# Dual_ESC_6-24V_3_6A_V4_Easy_EDA.net
KiCad netlist of a schematic drawn in EasyEDA Pro
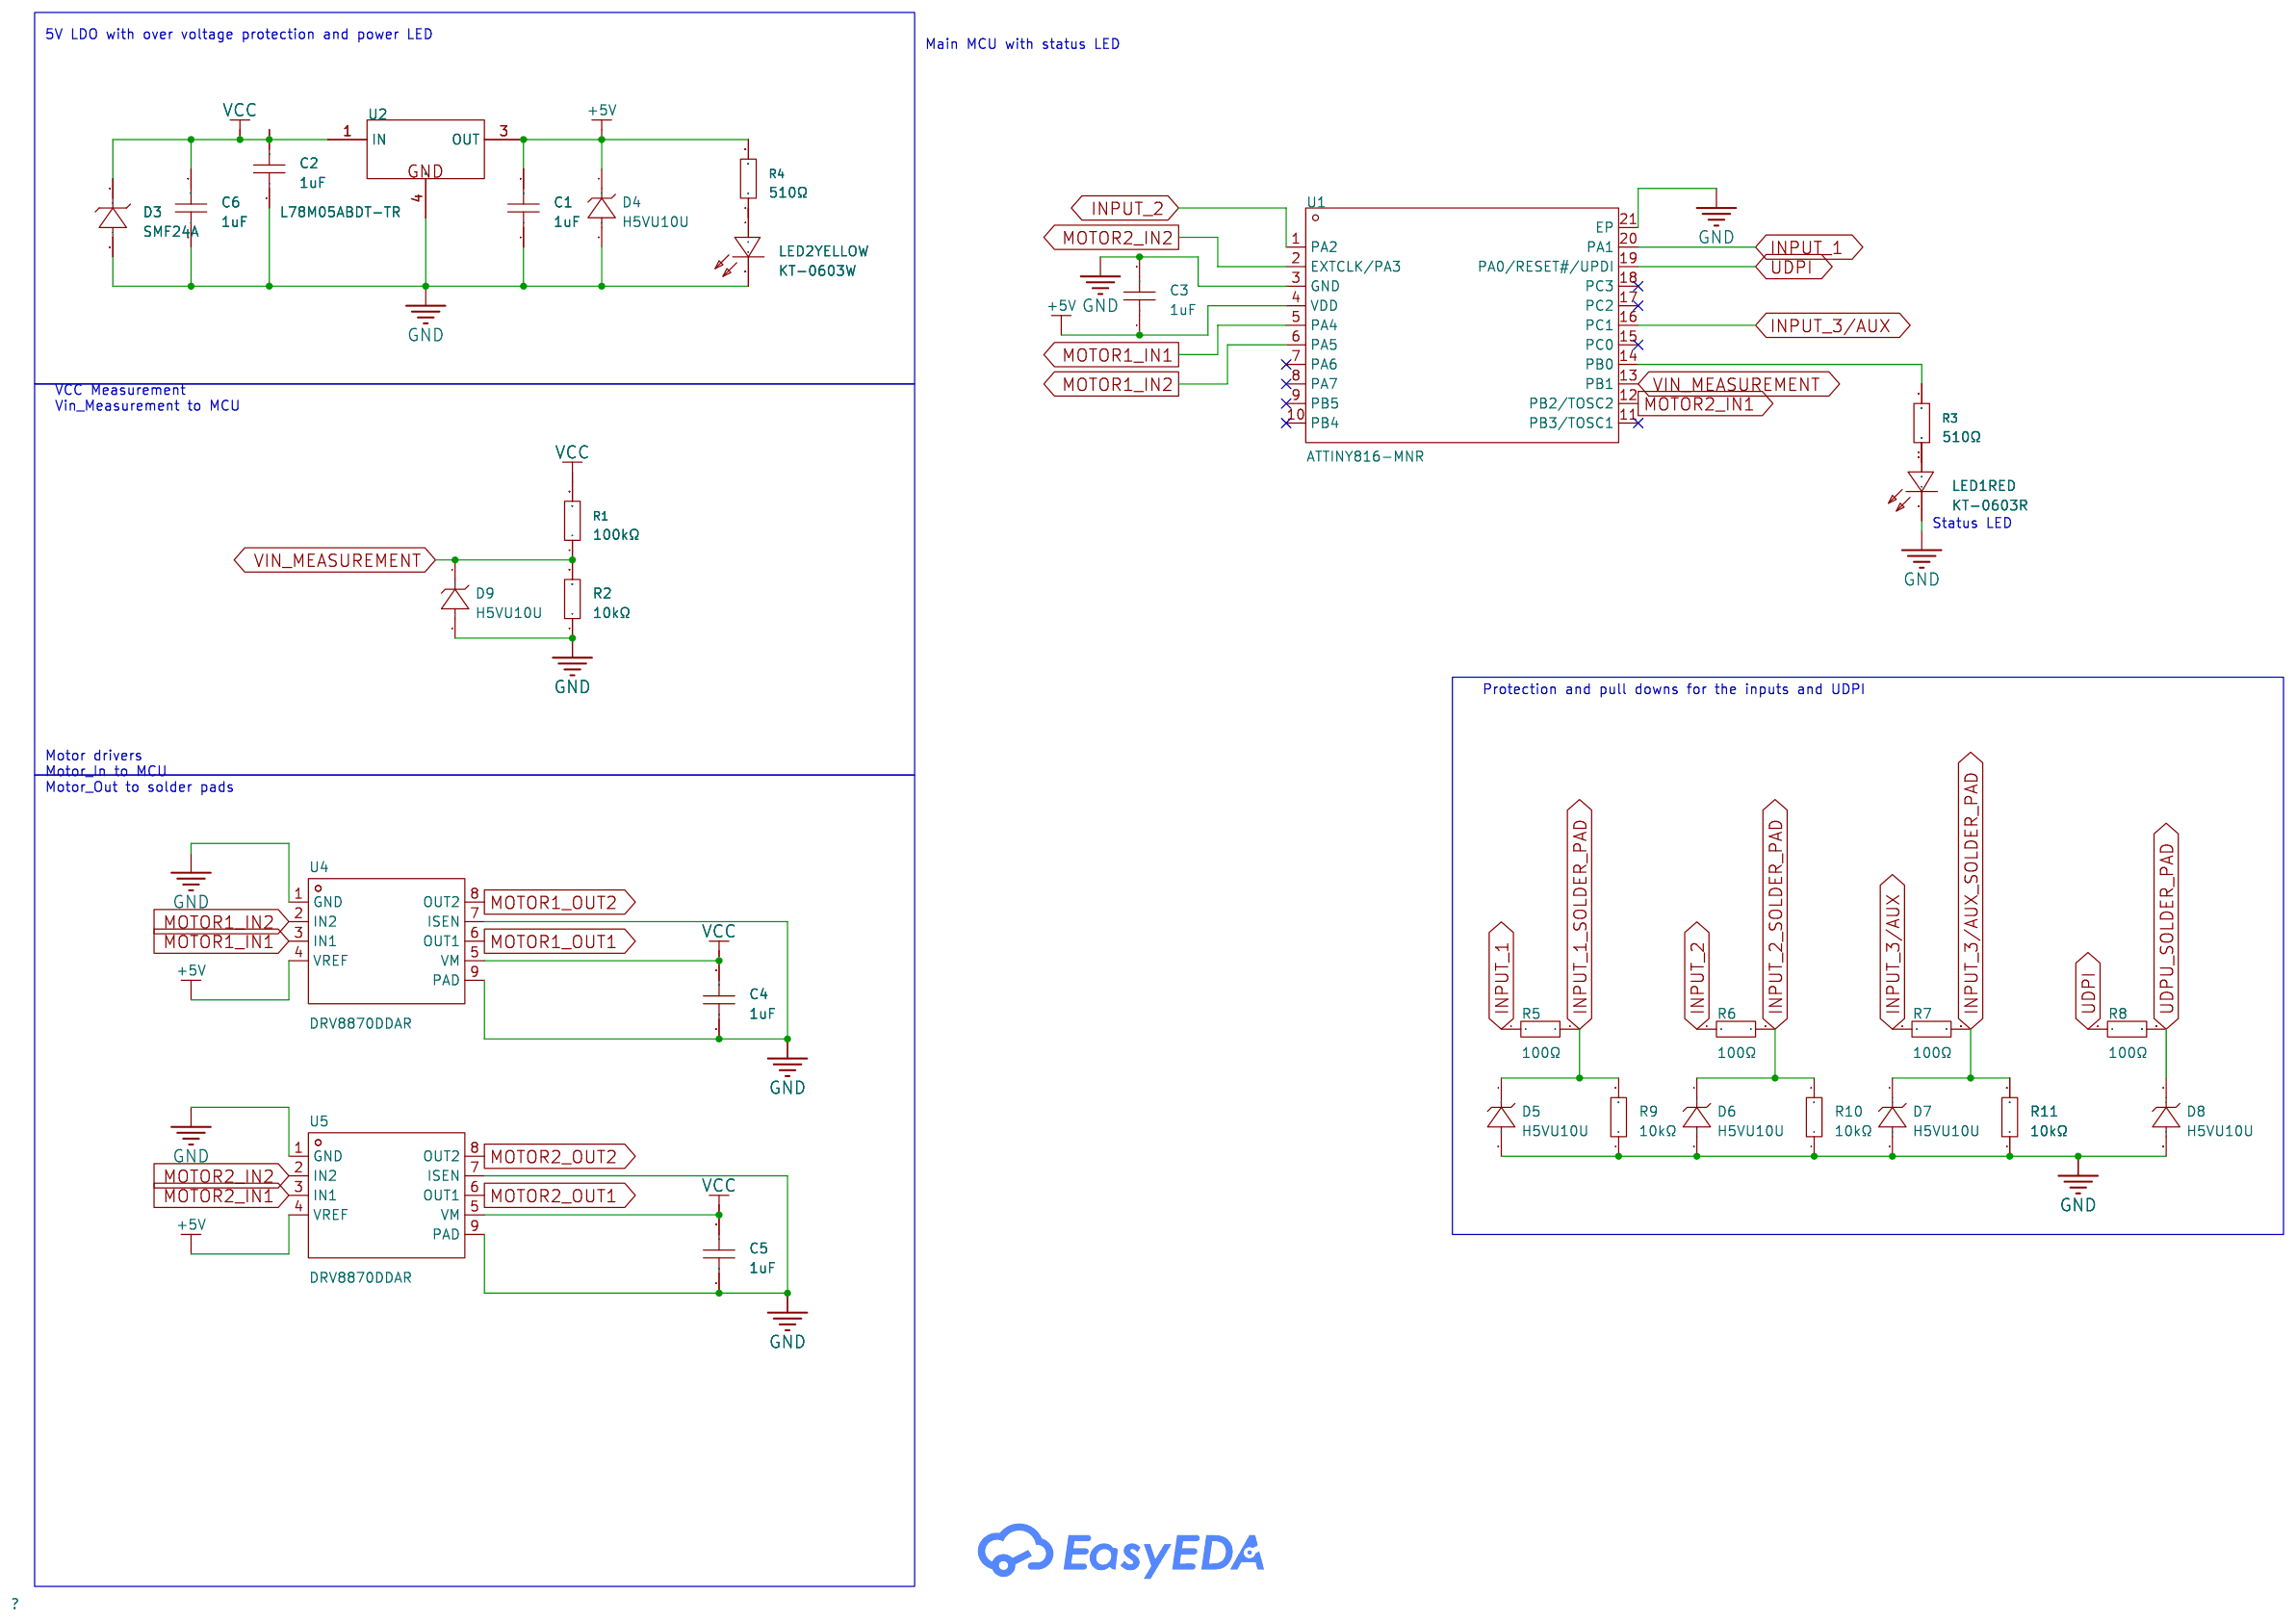
[diagram p0: schematic sheet]

(export (version "E")
  (design (tool "Eeschema 10.0.6"))
  (components
    (comp (ref "C1")
      (value "1uF")
      (footprint "easyedapro:C0402")
      (description "Capacitance:1uF Tolerance:±10% Tolerance:±10% Voltage Rating:25V Temperature Coefficient:X5R")
      (fields
        (field (name "Manufacturer Part") "CL05A105KA5NQNC")
        (field (name "Manufacturer") "SAMSUNG(三星)")
      )
      (libsource (lib "easyedapro") (part "CL05A105KA5NQNC"))
    )
    (comp (ref "C2")
      (value "1uF")
      (footprint "easyedapro:C0603")
      (description "Capacitance:1uF Tolerance:±10% Tolerance:±10% Voltage Rating:50V Temperature Coefficient:X5R")
      (fields
        (field (name "Manufacturer Part") "CL10A105KB8NNNC")
        (field (name "Manufacturer") "SAMSUNG(三星)")
      )
      (libsource (lib "easyedapro") (part "CL10A105KB8NNNC"))
    )
    (comp (ref "C3")
      (value "1uF")
      (footprint "easyedapro:C0402")
      (description "Capacitance:1uF Tolerance:±10% Tolerance:±10% Voltage Rating:25V Temperature Coefficient:X5R")
      (fields
        (field (name "Manufacturer Part") "CL05A105KA5NQNC")
        (field (name "Manufacturer") "SAMSUNG(三星)")
      )
      (libsource (lib "easyedapro") (part "CL05A105KA5NQNC"))
    )
    (comp (ref "C4")
      (value "1uF")
      (footprint "easyedapro:C0603")
      (description "Capacitance:1uF Tolerance:±10% Tolerance:±10% Voltage Rating:50V Temperature Coefficient:X5R")
      (fields
        (field (name "Manufacturer Part") "CL10A105KB8NNNC")
        (field (name "Manufacturer") "SAMSUNG(三星)")
      )
      (libsource (lib "easyedapro") (part "CL10A105KB8NNNC"))
    )
    (comp (ref "C5")
      (value "1uF")
      (footprint "easyedapro:C0603")
      (description "Capacitance:1uF Tolerance:±10% Tolerance:±10% Voltage Rating:50V Temperature Coefficient:X5R")
      (fields
        (field (name "Manufacturer Part") "CL10A105KB8NNNC")
        (field (name "Manufacturer") "SAMSUNG(三星)")
      )
      (libsource (lib "easyedapro") (part "CL10A105KB8NNNC"))
    )
    (comp (ref "C6")
      (value "1uF")
      (footprint "easyedapro:C0603")
      (description "Capacitance:1uF Tolerance:±10% Tolerance:±10% Voltage Rating:50V Temperature Coefficient:X5R")
      (fields
        (field (name "Manufacturer Part") "CL10A105KB8NNNC")
        (field (name "Manufacturer") "SAMSUNG(三星)")
      )
      (libsource (lib "easyedapro") (part "CL10A105KB8NNNC"))
    )
    (comp (ref "D3")
      (value "SMF24A")
      (footprint "easyedapro:SOD-123FL_L2.7-W1.8-LS3.8-RD")
      (fields (field (name "Manufacturer") "R+O(宏嘉诚)"))
      (libsource (lib "easyedapro") (part "SMF24A_C19077514"))
    )
    (comp (ref "D4")
      (value "H5VU10U")
      (footprint "easyedapro:DFN1006-2L-RD")
      (fields (field (name "Manufacturer") "R+O(宏嘉诚)"))
      (libsource (lib "easyedapro") (part "H5VU10U"))
    )
    (comp (ref "D5")
      (value "H5VU10U")
      (footprint "easyedapro:DFN1006-2L-RD")
      (fields (field (name "Manufacturer") "R+O(宏嘉诚)"))
      (libsource (lib "easyedapro") (part "H5VU10U"))
    )
    (comp (ref "D6")
      (value "H5VU10U")
      (footprint "easyedapro:DFN1006-2L-RD")
      (fields (field (name "Manufacturer") "R+O(宏嘉诚)"))
      (libsource (lib "easyedapro") (part "H5VU10U"))
    )
    (comp (ref "D7")
      (value "H5VU10U")
      (footprint "easyedapro:DFN1006-2L-RD")
      (fields (field (name "Manufacturer") "R+O(宏嘉诚)"))
      (libsource (lib "easyedapro") (part "H5VU10U"))
    )
    (comp (ref "D8")
      (value "H5VU10U")
      (footprint "easyedapro:DFN1006-2L-RD")
      (fields (field (name "Manufacturer") "R+O(宏嘉诚)"))
      (libsource (lib "easyedapro") (part "H5VU10U"))
    )
    (comp (ref "D9")
      (value "H5VU10U")
      (footprint "easyedapro:DFN1006-2L-RD")
      (fields (field (name "Manufacturer") "R+O(宏嘉诚)"))
      (libsource (lib "easyedapro") (part "H5VU10U"))
    )
    (comp (ref "LED1RED")
      (value "KT-0603R")
      (footprint "easyedapro:LED0603-RD")
      (fields (field (name "Manufacturer") "KENTO"))
      (libsource (lib "easyedapro") (part "KT-0603R"))
    )
    (comp (ref "LED2YELLOW")
      (value "KT-0603W")
      (footprint "easyedapro:LED0603-R-RD_WHITE")
      (fields (field (name "Manufacturer") "KENTO"))
      (libsource (lib "easyedapro") (part "0603White light_C2290"))
    )
    (comp (ref "R1")
      (value "100kΩ")
      (footprint "easyedapro:R0402")
      (fields
        (field (name "Manufacturer Part") "0402WGF1003TCE")
        (field (name "Manufacturer") "UNI-ROYAL(厚声)")
      )
      (libsource (lib "easyedapro") (part "0402WGF1003TCE"))
    )
    (comp (ref "R2")
      (value "10kΩ")
      (footprint "easyedapro:R0402")
      (fields
        (field (name "Manufacturer Part") "0402WGF1002TCE")
        (field (name "Manufacturer") "UNI-ROYAL(厚声)")
      )
      (libsource (lib "easyedapro") (part "0402WGF1002TCE"))
    )
    (comp (ref "R3")
      (value "510Ω")
      (footprint "easyedapro:R0402")
      (fields
        (field (name "Manufacturer Part") "0402WGF5100TCE")
        (field (name "Manufacturer") "UNI-ROYAL(厚声)")
      )
      (libsource (lib "easyedapro") (part "0402WGF5100TCE"))
    )
    (comp (ref "R4")
      (value "510Ω")
      (footprint "easyedapro:R0402")
      (fields
        (field (name "Manufacturer Part") "0402WGF5100TCE")
        (field (name "Manufacturer") "UNI-ROYAL(厚声)")
      )
      (libsource (lib "easyedapro") (part "0402WGF5100TCE"))
    )
    (comp (ref "R5")
      (value "100Ω")
      (footprint "easyedapro:R0402")
      (fields
        (field (name "Manufacturer Part") "0402WGF1000TCE")
        (field (name "Manufacturer") "UNI-ROYAL(厚声)")
      )
      (libsource (lib "easyedapro") (part "0402WGF1000TCE"))
    )
    (comp (ref "R6")
      (value "100Ω")
      (footprint "easyedapro:R0402")
      (fields
        (field (name "Manufacturer Part") "0402WGF1000TCE")
        (field (name "Manufacturer") "UNI-ROYAL(厚声)")
      )
      (libsource (lib "easyedapro") (part "0402WGF1000TCE"))
    )
    (comp (ref "R7")
      (value "100Ω")
      (footprint "easyedapro:R0402")
      (fields
        (field (name "Manufacturer Part") "0402WGF1000TCE")
        (field (name "Manufacturer") "UNI-ROYAL(厚声)")
      )
      (libsource (lib "easyedapro") (part "0402WGF1000TCE"))
    )
    (comp (ref "R8")
      (value "100Ω")
      (footprint "easyedapro:R0402")
      (fields
        (field (name "Manufacturer Part") "0402WGF1000TCE")
        (field (name "Manufacturer") "UNI-ROYAL(厚声)")
      )
      (libsource (lib "easyedapro") (part "0402WGF1000TCE"))
    )
    (comp (ref "R9")
      (value "10kΩ")
      (footprint "easyedapro:R0402")
      (fields
        (field (name "Manufacturer Part") "0402WGF1002TCE")
        (field (name "Manufacturer") "UNI-ROYAL(厚声)")
      )
      (libsource (lib "easyedapro") (part "0402WGF1002TCE"))
    )
    (comp (ref "R10")
      (value "10kΩ")
      (footprint "easyedapro:R0402")
      (fields
        (field (name "Manufacturer Part") "0402WGF1002TCE")
        (field (name "Manufacturer") "UNI-ROYAL(厚声)")
      )
      (libsource (lib "easyedapro") (part "0402WGF1002TCE"))
    )
    (comp (ref "R11")
      (value "10kΩ")
      (footprint "easyedapro:R0402")
      (fields
        (field (name "Manufacturer Part") "0402WGF1002TCE")
        (field (name "Manufacturer") "UNI-ROYAL(厚声)")
      )
      (libsource (lib "easyedapro") (part "0402WGF1002TCE"))
    )
    (comp (ref "U1")
      (value "ATTINY816-MNR")
      (fields (field (name "Manufacturer") "MICROCHIP(美国微芯)"))
      (libsource (lib "easyedapro") (part "ATTINY1616-MNR"))
    )
    (comp (ref "U2")
      (value "L78M05ABDT-TR")
      (footprint "easyedapro:TO-252-2_L6.5-W6.1-P4.58-LS10.0-TL")
      (fields (field (name "Manufacturer") "ST(意法半导体)"))
      (libsource (lib "easyedapro") (part "L78M05ABDT-TR"))
    )
    (comp (ref "U4")
      (value "DRV8870DDAR")
      (footprint "easyedapro:HSOP-8_L5.0-W4.0-P1.27-LS6.2-BL-EP")
      (fields (field (name "Manufacturer") "TI(德州仪器)"))
      (libsource (lib "easyedapro") (part "DRV8870DDAR"))
    )
    (comp (ref "U5")
      (value "DRV8870DDAR")
      (footprint "easyedapro:HSOP-8_L5.0-W4.0-P1.27-LS6.2-BL-EP")
      (fields (field (name "Manufacturer") "TI(德州仪器)"))
      (libsource (lib "easyedapro") (part "DRV8870DDAR"))
    )
  )
  (nets
    (net (code "1") (name "+5V") (class "Default")
      (node (ref "C1") (pin "2") (pinfunction "2_2") (pintype "unspecified"))
      (node (ref "C3") (pin "1") (pinfunction "1_1") (pintype "unspecified"))
      (node (ref "D4") (pin "1") (pinfunction "K_1") (pintype "unspecified"))
      (node (ref "R4") (pin "2") (pinfunction "2_2") (pintype "input"))
      (node (ref "U1") (pin "4") (pinfunction "VDD_4") (pintype "unspecified"))
      (node (ref "U2") (pin "3") (pinfunction "OUT_3") (pintype "unspecified"))
      (node (ref "U4") (pin "4") (pinfunction "VREF_4") (pintype "unspecified"))
      (node (ref "U5") (pin "4") (pinfunction "VREF_4") (pintype "unspecified"))
    )
    (net (code "2") (name "GND") (class "Default")
      (node (ref "C1") (pin "1") (pinfunction "1_1") (pintype "unspecified"))
      (node (ref "C2") (pin "1") (pinfunction "1_1") (pintype "unspecified"))
      (node (ref "C3") (pin "2") (pinfunction "2_2") (pintype "unspecified"))
      (node (ref "C4") (pin "1") (pinfunction "1_1") (pintype "unspecified"))
      (node (ref "C5") (pin "1") (pinfunction "1_1") (pintype "unspecified"))
      (node (ref "C6") (pin "1") (pinfunction "1_1") (pintype "unspecified"))
      (node (ref "D3") (pin "2") (pinfunction "A_2") (pintype "unspecified"))
      (node (ref "D4") (pin "2") (pinfunction "A_2") (pintype "unspecified"))
      (node (ref "D5") (pin "2") (pinfunction "A_2") (pintype "unspecified"))
      (node (ref "D6") (pin "2") (pinfunction "A_2") (pintype "unspecified"))
      (node (ref "D7") (pin "2") (pinfunction "A_2") (pintype "unspecified"))
      (node (ref "D8") (pin "2") (pinfunction "A_2") (pintype "unspecified"))
      (node (ref "D9") (pin "2") (pinfunction "A_2") (pintype "unspecified"))
      (node (ref "LED1RED") (pin "1") (pinfunction "K_1") (pintype "unspecified"))
      (node (ref "LED2YELLOW") (pin "2") (pinfunction "K_2") (pintype "unspecified"))
      (node (ref "R10") (pin "1") (pinfunction "1_1") (pintype "input"))
      (node (ref "R11") (pin "1") (pinfunction "1_1") (pintype "input"))
      (node (ref "R2") (pin "1") (pinfunction "1_1") (pintype "input"))
      (node (ref "R9") (pin "1") (pinfunction "1_1") (pintype "input"))
      (node (ref "U1") (pin "21") (pinfunction "EP_21") (pintype "unspecified"))
      (node (ref "U1") (pin "3") (pinfunction "GND_3") (pintype "unspecified"))
      (node (ref "U2") (pin "4") (pinfunction "GND_4") (pintype "unspecified"))
      (node (ref "U4") (pin "1") (pinfunction "GND_1") (pintype "unspecified"))
      (node (ref "U4") (pin "7") (pinfunction "ISEN_7") (pintype "unspecified"))
      (node (ref "U4") (pin "9") (pinfunction "PAD_9") (pintype "unspecified"))
      (node (ref "U5") (pin "1") (pinfunction "GND_1") (pintype "unspecified"))
      (node (ref "U5") (pin "7") (pinfunction "ISEN_7") (pintype "unspecified"))
      (node (ref "U5") (pin "9") (pinfunction "PAD_9") (pintype "unspecified"))
    )
    (net (code "3") (name "INPUT_1") (class "Default")
      (node (ref "R5") (pin "1") (pinfunction "1_1") (pintype "input"))
      (node (ref "U1") (pin "20") (pinfunction "PA1_20") (pintype "unspecified"))
    )
    (net (code "4") (name "INPUT_1_SOLDER_PAD") (class "Default")
      (node (ref "D5") (pin "1") (pinfunction "K_1") (pintype "unspecified"))
      (node (ref "R5") (pin "2") (pinfunction "2_2") (pintype "input"))
      (node (ref "R9") (pin "2") (pinfunction "2_2") (pintype "input"))
    )
    (net (code "5") (name "INPUT_2") (class "Default")
      (node (ref "R6") (pin "1") (pinfunction "1_1") (pintype "input"))
      (node (ref "U1") (pin "1") (pinfunction "PA2_1") (pintype "unspecified"))
    )
    (net (code "6") (name "INPUT_2_SOLDER_PAD") (class "Default")
      (node (ref "D6") (pin "1") (pinfunction "K_1") (pintype "unspecified"))
      (node (ref "R10") (pin "2") (pinfunction "2_2") (pintype "input"))
      (node (ref "R6") (pin "2") (pinfunction "2_2") (pintype "input"))
    )
    (net (code "7") (name "INPUT_3{slash}AUX") (class "Default")
      (node (ref "R7") (pin "1") (pinfunction "1_1") (pintype "input"))
      (node (ref "U1") (pin "16") (pinfunction "PC1_16") (pintype "unspecified"))
    )
    (net (code "8") (name "INPUT_3{slash}AUX_SOLDER_PAD") (class "Default")
      (node (ref "D7") (pin "1") (pinfunction "K_1") (pintype "unspecified"))
      (node (ref "R11") (pin "2") (pinfunction "2_2") (pintype "input"))
      (node (ref "R7") (pin "2") (pinfunction "2_2") (pintype "input"))
    )
    (net (code "9") (name "MOTOR1_IN1") (class "Default")
      (node (ref "U1") (pin "5") (pinfunction "PA4_5") (pintype "unspecified"))
      (node (ref "U4") (pin "3") (pinfunction "IN1_3") (pintype "unspecified"))
    )
    (net (code "10") (name "MOTOR1_IN2") (class "Default")
      (node (ref "U1") (pin "6") (pinfunction "PA5_6") (pintype "unspecified"))
      (node (ref "U4") (pin "2") (pinfunction "IN2_2") (pintype "unspecified"))
    )
    (net (code "11") (name "MOTOR1_OUT1") (class "Default")
      (node (ref "U4") (pin "6") (pinfunction "OUT1_6") (pintype "unspecified"))
    )
    (net (code "12") (name "MOTOR1_OUT2") (class "Default")
      (node (ref "U4") (pin "8") (pinfunction "OUT2_8") (pintype "unspecified"))
    )
    (net (code "13") (name "MOTOR2_IN1") (class "Default")
      (node (ref "U1") (pin "12") (pinfunction "PB2/TOSC2_12") (pintype "unspecified"))
      (node (ref "U5") (pin "3") (pinfunction "IN1_3") (pintype "unspecified"))
    )
    (net (code "14") (name "MOTOR2_IN2") (class "Default")
      (node (ref "U1") (pin "2") (pinfunction "EXTCLK/PA3_2") (pintype "unspecified"))
      (node (ref "U5") (pin "2") (pinfunction "IN2_2") (pintype "unspecified"))
    )
    (net (code "15") (name "MOTOR2_OUT1") (class "Default")
      (node (ref "U5") (pin "6") (pinfunction "OUT1_6") (pintype "unspecified"))
    )
    (net (code "16") (name "MOTOR2_OUT2") (class "Default")
      (node (ref "U5") (pin "8") (pinfunction "OUT2_8") (pintype "unspecified"))
    )
    (net (code "17") (name "Net-(LED1RED-A)") (class "Default")
      (node (ref "LED1RED") (pin "2") (pinfunction "A_2") (pintype "unspecified"))
      (node (ref "R3") (pin "1") (pinfunction "1_1") (pintype "input"))
    )
    (net (code "18") (name "Net-(LED2YELLOW-A)") (class "Default")
      (node (ref "LED2YELLOW") (pin "1") (pinfunction "A_1") (pintype "unspecified"))
      (node (ref "R4") (pin "1") (pinfunction "1_1") (pintype "input"))
    )
    (net (code "19") (name "Net-(U1-PB0)") (class "Default")
      (node (ref "R3") (pin "2") (pinfunction "2_2") (pintype "input"))
      (node (ref "U1") (pin "14") (pinfunction "PB0_14") (pintype "unspecified"))
    )
    (net (code "20") (name "UDPI") (class "Default")
      (node (ref "R8") (pin "1") (pinfunction "1_1") (pintype "input"))
      (node (ref "U1") (pin "19") (pinfunction "PA0/RESET#/UPDI_19") (pintype "unspecified"))
    )
    (net (code "21") (name "UDPU_SOLDER_PAD") (class "Default")
      (node (ref "D8") (pin "1") (pinfunction "K_1") (pintype "unspecified"))
      (node (ref "R8") (pin "2") (pinfunction "2_2") (pintype "input"))
    )
    (net (code "22") (name "VCC") (class "Default")
      (node (ref "C2") (pin "2") (pinfunction "2_2") (pintype "unspecified"))
      (node (ref "C4") (pin "2") (pinfunction "2_2") (pintype "unspecified"))
      (node (ref "C5") (pin "2") (pinfunction "2_2") (pintype "unspecified"))
      (node (ref "C6") (pin "2") (pinfunction "2_2") (pintype "unspecified"))
      (node (ref "D3") (pin "1") (pinfunction "K_1") (pintype "unspecified"))
      (node (ref "R1") (pin "2") (pinfunction "2_2") (pintype "input"))
      (node (ref "U2") (pin "1") (pinfunction "IN_1") (pintype "unspecified"))
      (node (ref "U4") (pin "5") (pinfunction "VM_5") (pintype "unspecified"))
      (node (ref "U5") (pin "5") (pinfunction "VM_5") (pintype "unspecified"))
    )
    (net (code "23") (name "VIN_MEASUREMENT") (class "Default")
      (node (ref "D9") (pin "1") (pinfunction "K_1") (pintype "unspecified"))
      (node (ref "R1") (pin "1") (pinfunction "1_1") (pintype "input"))
      (node (ref "R2") (pin "2") (pinfunction "2_2") (pintype "input"))
      (node (ref "U1") (pin "13") (pinfunction "PB1_13") (pintype "unspecified"))
    )
    (net (code "24") (name "unconnected-(U1-PA6-Pad7)") (class "Default")
      (node (ref "U1") (pin "7") (pinfunction "PA6_7") (pintype "unspecified+no_connect"))
    )
    (net (code "25") (name "unconnected-(U1-PA7-Pad8)") (class "Default")
      (node (ref "U1") (pin "8") (pinfunction "PA7_8") (pintype "unspecified+no_connect"))
    )
    (net (code "26") (name "unconnected-(U1-PB3{slash}TOSC1-Pad11)") (class "Default")
      (node (ref "U1") (pin "11") (pinfunction "PB3/TOSC1_11") (pintype "unspecified+no_connect"))
    )
    (net (code "27") (name "unconnected-(U1-PB4-Pad10)") (class "Default")
      (node (ref "U1") (pin "10") (pinfunction "PB4_10") (pintype "unspecified+no_connect"))
    )
    (net (code "28") (name "unconnected-(U1-PB5-Pad9)") (class "Default")
      (node (ref "U1") (pin "9") (pinfunction "PB5_9") (pintype "unspecified+no_connect"))
    )
    (net (code "29") (name "unconnected-(U1-PC0-Pad15)") (class "Default")
      (node (ref "U1") (pin "15") (pinfunction "PC0_15") (pintype "unspecified+no_connect"))
    )
    (net (code "30") (name "unconnected-(U1-PC2-Pad17)") (class "Default")
      (node (ref "U1") (pin "17") (pinfunction "PC2_17") (pintype "unspecified+no_connect"))
    )
    (net (code "31") (name "unconnected-(U1-PC3-Pad18)") (class "Default")
      (node (ref "U1") (pin "18") (pinfunction "PC3_18") (pintype "unspecified+no_connect"))
    )
  )
)
